# EMAT_K1.net
KiCad netlist of a schematic drawn in Altium Designer
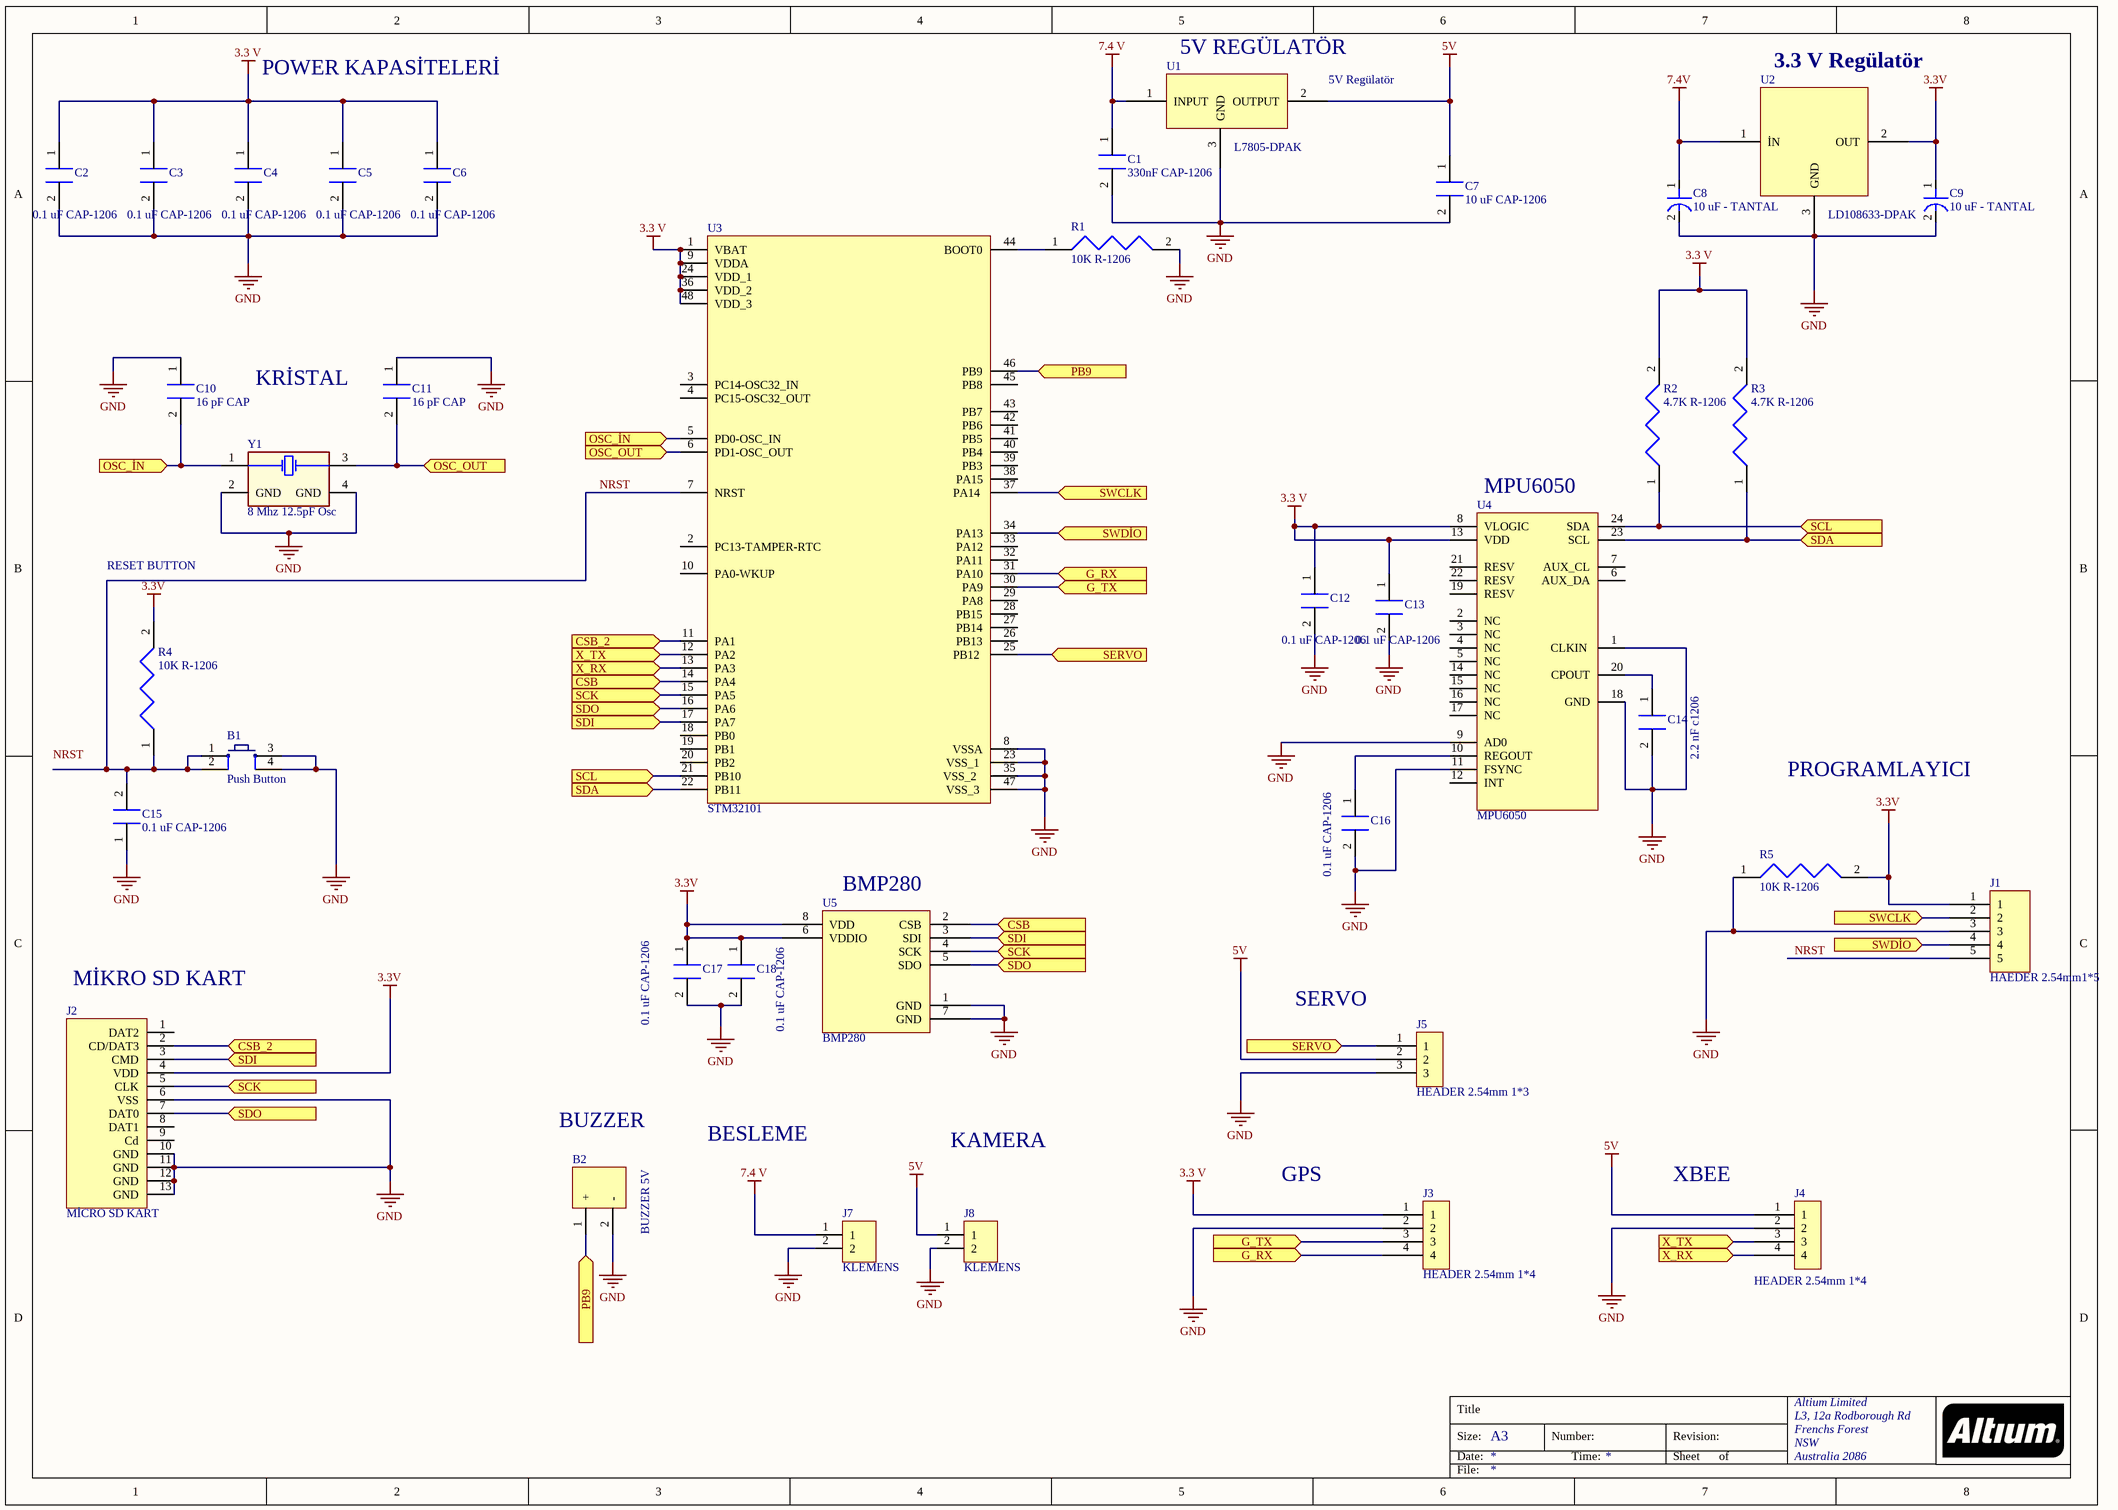
[diagram p0: ŞEMATİK1.SchDoc]

(export (version "E")
  (design (tool "Eeschema 10.0.6"))
  (components
    (comp (ref "B1")
      (value "Push Button")
      (footprint "PUSH BUTTON")
      (description "Smd Push Button")
      (libsource (lib "ŞEMATİK KÜTÜPHANE") (part "Push Button"))
    )
    (comp (ref "B2")
      (value "BUZZER 5V")
      (footprint "BUZZER")
      (description "1*2")
      (libsource (lib "ŞEMATİK KÜTÜPHANE") (part "BUZZER 5V"))
    )
    (comp (ref "C1")
      (value "330nF CAP-1206")
      (footprint "CAP-1206")
      (description "330nF 1206")
      (libsource (lib "ŞEMATİK KÜTÜPHANE") (part "330nF CAP-1206"))
    )
    (comp (ref "C2")
      (value "0.1 uF CAP-1206")
      (footprint "CAP-1206")
      (description "0.1 uF 1206")
      (libsource (lib "ŞEMATİK KÜTÜPHANE") (part "0.1 uF CAP-1206"))
    )
    (comp (ref "C3")
      (value "0.1 uF CAP-1206")
      (footprint "CAP-1206")
      (description "0.1 uF 1206")
      (libsource (lib "ŞEMATİK KÜTÜPHANE") (part "0.1 uF CAP-1206"))
    )
    (comp (ref "C4")
      (value "0.1 uF CAP-1206")
      (footprint "CAP-1206")
      (description "0.1 uF 1206")
      (libsource (lib "ŞEMATİK KÜTÜPHANE") (part "0.1 uF CAP-1206"))
    )
    (comp (ref "C5")
      (value "0.1 uF CAP-1206")
      (footprint "CAP-1206")
      (description "0.1 uF 1206")
      (libsource (lib "ŞEMATİK KÜTÜPHANE") (part "0.1 uF CAP-1206"))
    )
    (comp (ref "C6")
      (value "0.1 uF CAP-1206")
      (footprint "CAP-1206")
      (description "0.1 uF 1206")
      (libsource (lib "ŞEMATİK KÜTÜPHANE") (part "0.1 uF CAP-1206"))
    )
    (comp (ref "C7")
      (value "10 uF CAP-1206")
      (footprint "CAP-1206")
      (libsource (lib "ŞEMATİK KÜTÜPHANE") (part "10 uF CAP-1206"))
    )
    (comp (ref "C8")
      (value "10 uF - TANTAL")
      (footprint "CAP-1206 TANTAL")
      (description "KUTUPLU")
      (libsource (lib "ŞEMATİK KÜTÜPHANE") (part "10 uF - TANTAL"))
    )
    (comp (ref "C9")
      (value "10 uF - TANTAL")
      (footprint "CAP-1206 TANTAL")
      (description "KUTUPLU")
      (libsource (lib "ŞEMATİK KÜTÜPHANE") (part "10 uF - TANTAL"))
    )
    (comp (ref "C10")
      (value "16 pF CAP")
      (footprint "16pF CAP")
      (description "16pF Capasitör")
      (libsource (lib "ŞEMATİK KÜTÜPHANE") (part "16 pF CAP"))
    )
    (comp (ref "C11")
      (value "16 pF CAP")
      (footprint "16pF CAP")
      (description "16pF Capasitör")
      (libsource (lib "ŞEMATİK KÜTÜPHANE") (part "16 pF CAP"))
    )
    (comp (ref "C12")
      (value "0.1 uF CAP-1206")
      (footprint "CAP-1206")
      (description "0.1 uF 1206")
      (libsource (lib "ŞEMATİK KÜTÜPHANE") (part "0.1 uF CAP-1206"))
    )
    (comp (ref "C13")
      (value "0.1 uF CAP-1206")
      (footprint "CAP-1206")
      (description "0.1 uF 1206")
      (libsource (lib "ŞEMATİK KÜTÜPHANE") (part "0.1 uF CAP-1206"))
    )
    (comp (ref "C14")
      (value "2.2 nF c1206")
      (footprint "CAP-1206")
      (libsource (lib "ŞEMATİK KÜTÜPHANE") (part "2.2 nF c1206"))
    )
    (comp (ref "C15")
      (value "0.1 uF CAP-1206")
      (footprint "CAP-1206")
      (description "0.1 uF 1206")
      (libsource (lib "ŞEMATİK KÜTÜPHANE") (part "0.1 uF CAP-1206"))
    )
    (comp (ref "C16")
      (value "0.1 uF CAP-1206")
      (footprint "CAP-1206")
      (description "0.1 uF 1206")
      (libsource (lib "ŞEMATİK KÜTÜPHANE") (part "0.1 uF CAP-1206"))
    )
    (comp (ref "C17")
      (value "0.1 uF CAP-1206")
      (footprint "CAP-1206")
      (description "0.1 uF 1206")
      (libsource (lib "ŞEMATİK KÜTÜPHANE") (part "0.1 uF CAP-1206"))
    )
    (comp (ref "C18")
      (value "0.1 uF CAP-1206")
      (footprint "CAP-1206")
      (description "0.1 uF 1206")
      (libsource (lib "ŞEMATİK KÜTÜPHANE") (part "0.1 uF CAP-1206"))
    )
    (comp (ref "J1")
      (value "HAEDER 2.54mm1*5")
      (footprint "FEMALE HEADER 1*5 2.54 MM")
      (description "5 PİNLİ")
      (libsource (lib "ŞEMATİK KÜTÜPHANE") (part "HAEDER 2.54mm1*5"))
    )
    (comp (ref "J2")
      (value "MİCRO SD KART")
      (footprint "MİCRO SD KART")
      (description "SD HOLDER")
      (libsource (lib "ŞEMATİK KÜTÜPHANE") (part "MİCRO SD KART"))
    )
    (comp (ref "J3")
      (value "HEADER 2.54mm 1*4")
      (footprint "FEMALE HEADER 1*4 2.54MM")
      (description "4 PİNLİ")
      (libsource (lib "ŞEMATİK KÜTÜPHANE") (part "HEADER 2.54mm 1*4"))
    )
    (comp (ref "J4")
      (value "HEADER 2.54mm 1*4")
      (footprint "FEMALE HEADER 1*4 2.54MM")
      (description "4 PİNLİ")
      (libsource (lib "ŞEMATİK KÜTÜPHANE") (part "HEADER 2.54mm 1*4"))
    )
    (comp (ref "J5")
      (value "HEADER 2.54mm 1*3")
      (footprint "FEMALE HEADER 1*3 2.54MM")
      (description "3 PİNLİ")
      (libsource (lib "ŞEMATİK KÜTÜPHANE") (part "HEADER 2.54mm 1*3"))
    )
    (comp (ref "J7")
      (value "KLEMENS")
      (footprint "KLEMENS 1*2 / 3.5mm")
      (description "1*2/ 3.5MM")
      (libsource (lib "ŞEMATİK KÜTÜPHANE") (part "KLEMENS"))
    )
    (comp (ref "J8")
      (value "KLEMENS")
      (footprint "KLEMENS 1*2 / 3.5mm")
      (description "1*2/ 3.5MM")
      (libsource (lib "ŞEMATİK KÜTÜPHANE") (part "KLEMENS"))
    )
    (comp (ref "R1")
      (value "10K R-1206")
      (footprint "RES 1206")
      (libsource (lib "ŞEMATİK KÜTÜPHANE") (part "10K R-1206"))
    )
    (comp (ref "R2")
      (value "4.7K R-1206")
      (footprint "RES 1206")
      (libsource (lib "ŞEMATİK KÜTÜPHANE") (part "4.7K R-1206"))
    )
    (comp (ref "R3")
      (value "4.7K R-1206")
      (footprint "RES 1206")
      (libsource (lib "ŞEMATİK KÜTÜPHANE") (part "4.7K R-1206"))
    )
    (comp (ref "R4")
      (value "10K R-1206")
      (footprint "RES 1206")
      (libsource (lib "ŞEMATİK KÜTÜPHANE") (part "10K R-1206"))
    )
    (comp (ref "R5")
      (value "10K R-1206")
      (footprint "RES 1206")
      (libsource (lib "ŞEMATİK KÜTÜPHANE") (part "10K R-1206"))
    )
    (comp (ref "U1")
      (value "L7805-DPAK")
      (footprint "DPAKL7805 REGULATOR")
      (description "5V REGÜLATÖR DPAK")
      (libsource (lib "ŞEMATİK KÜTÜPHANE") (part "L7805-DPAK"))
    )
    (comp (ref "U2")
      (value "LD108633-DPAK")
      (footprint "DPAKL7805 REGULATOR")
      (description "3.3V  REGÜLATÖR")
      (libsource (lib "ŞEMATİK KÜTÜPHANE") (part "LD108633-DPAK"))
    )
    (comp (ref "U3")
      (value "STM32101")
      (footprint "FQP48")
      (description "STM32F48 101 İŞLEMCİ")
      (libsource (lib "ŞEMATİK KÜTÜPHANE") (part "STM32101"))
    )
    (comp (ref "U4")
      (value "MPU6050")
      (footprint "MPU6050-QFN")
      (description "QFNP 6*6 İŞLEMCİ")
      (libsource (lib "ŞEMATİK KÜTÜPHANE") (part "MPU6050"))
    )
    (comp (ref "U5")
      (value "BMP280")
      (footprint "BMP-280")
      (description "BMP280 SENSOR")
      (libsource (lib "ŞEMATİK KÜTÜPHANE") (part "BMP280"))
    )
    (comp (ref "Y1")
      (value "8 Mhz 12.5pF Osc")
      (footprint "8 Mhz 12.5pF OSC")
      (libsource (lib "ŞEMATİK KÜTÜPHANE") (part "8 Mhz 12.5pF Osc"))
    )
  )
  (nets
    (net (code "1") (name "/CSB") (class "Default")
      (node (ref "U3") (pin "14") (pinfunction "PA4_14") (pintype "passive"))
      (node (ref "U5") (pin "2") (pinfunction "CSB_2") (pintype "passive"))
    )
    (net (code "2") (name "/CSB_2") (class "Default")
      (node (ref "J2") (pin "2") (pinfunction "CD/DAT3_2") (pintype "passive"))
      (node (ref "U3") (pin "11") (pinfunction "PA1_11") (pintype "passive"))
    )
    (net (code "3") (name "/G_RX") (class "Default")
      (node (ref "J3") (pin "4") (pinfunction "4_4") (pintype "passive"))
      (node (ref "U3") (pin "31") (pinfunction "PA10_31") (pintype "passive"))
    )
    (net (code "4") (name "/G_TX") (class "Default")
      (node (ref "J3") (pin "3") (pinfunction "3_3") (pintype "passive"))
      (node (ref "U3") (pin "30") (pinfunction "PA9_30") (pintype "passive"))
    )
    (net (code "5") (name "/NRST") (class "Default")
      (node (ref "B1") (pin "1") (pinfunction "1_1") (pintype "passive"))
      (node (ref "B1") (pin "2") (pinfunction "2_2") (pintype "passive"))
      (node (ref "C15") (pin "2") (pinfunction "2_2") (pintype "passive"))
      (node (ref "J1") (pin "5") (pinfunction "5_5") (pintype "passive"))
      (node (ref "R4") (pin "1") (pinfunction "1_1") (pintype "passive"))
      (node (ref "U3") (pin "7") (pinfunction "NRST_7") (pintype "passive"))
    )
    (net (code "6") (name "/OSC_OUT") (class "Default")
      (node (ref "C11") (pin "2") (pinfunction "2_2") (pintype "passive"))
      (node (ref "U3") (pin "6") (pinfunction "PD1-OSC_OUT_6") (pintype "passive"))
      (node (ref "Y1") (pin "3") (pintype "passive"))
    )
    (net (code "7") (name "/OSC_İN") (class "Default")
      (node (ref "C10") (pin "2") (pinfunction "2_2") (pintype "passive"))
      (node (ref "U3") (pin "5") (pinfunction "PD0-OSC_IN_5") (pintype "passive"))
      (node (ref "Y1") (pin "1") (pintype "power_in"))
    )
    (net (code "8") (name "/PB9") (class "Default")
      (node (ref "B2") (pin "1") (pinfunction "+_1") (pintype "passive"))
      (node (ref "U3") (pin "46") (pinfunction "PB9_46") (pintype "passive"))
    )
    (net (code "9") (name "/SCK") (class "Default")
      (node (ref "J2") (pin "5") (pinfunction "CLK_5") (pintype "passive"))
      (node (ref "U3") (pin "15") (pinfunction "PA5_15") (pintype "passive"))
      (node (ref "U5") (pin "4") (pinfunction "SCK_4") (pintype "passive"))
    )
    (net (code "10") (name "/SCL") (class "Default")
      (node (ref "R2") (pin "1") (pinfunction "1_1") (pintype "passive"))
      (node (ref "U3") (pin "21") (pinfunction "PB10_21") (pintype "passive"))
      (node (ref "U4") (pin "24") (pinfunction "SDA_24") (pintype "passive"))
    )
    (net (code "11") (name "/SDA") (class "Default")
      (node (ref "R3") (pin "1") (pinfunction "1_1") (pintype "passive"))
      (node (ref "U3") (pin "22") (pinfunction "PB11_22") (pintype "passive"))
      (node (ref "U4") (pin "23") (pinfunction "SCL_23") (pintype "passive"))
    )
    (net (code "12") (name "/SDI") (class "Default")
      (node (ref "J2") (pin "3") (pinfunction "CMD_3") (pintype "passive"))
      (node (ref "U3") (pin "17") (pinfunction "PA7_17") (pintype "passive"))
      (node (ref "U5") (pin "3") (pinfunction "SDI_3") (pintype "passive"))
    )
    (net (code "13") (name "/SDO") (class "Default")
      (node (ref "J2") (pin "7") (pinfunction "DAT0_7") (pintype "passive"))
      (node (ref "U3") (pin "16") (pinfunction "PA6_16") (pintype "passive"))
      (node (ref "U5") (pin "5") (pinfunction "SDO_5") (pintype "passive"))
    )
    (net (code "14") (name "/SERVO") (class "Default")
      (node (ref "J5") (pin "1") (pinfunction "1_1") (pintype "passive"))
      (node (ref "U3") (pin "25") (pinfunction "PB12_25") (pintype "passive"))
    )
    (net (code "15") (name "/SWCLK") (class "Default")
      (node (ref "J1") (pin "2") (pinfunction "2_2") (pintype "passive"))
      (node (ref "U3") (pin "37") (pinfunction "PA14_37") (pintype "passive"))
    )
    (net (code "16") (name "/SWDİO") (class "Default")
      (node (ref "J1") (pin "4") (pinfunction "4_4") (pintype "passive"))
      (node (ref "U3") (pin "34") (pinfunction "PA13_34") (pintype "passive"))
    )
    (net (code "17") (name "/X_RX") (class "Default")
      (node (ref "J4") (pin "4") (pinfunction "4_4") (pintype "passive"))
      (node (ref "U3") (pin "13") (pinfunction "PA3_13") (pintype "passive"))
    )
    (net (code "18") (name "/X_TX") (class "Default")
      (node (ref "J4") (pin "3") (pinfunction "3_3") (pintype "passive"))
      (node (ref "U3") (pin "12") (pinfunction "PA2_12") (pintype "passive"))
    )
    (net (code "19") (name "3.3 V") (class "Default")
      (node (ref "C12") (pin "1") (pinfunction "1_1") (pintype "passive"))
      (node (ref "C13") (pin "1") (pinfunction "1_1") (pintype "passive"))
      (node (ref "C2") (pin "1") (pinfunction "1_1") (pintype "passive"))
      (node (ref "C3") (pin "1") (pinfunction "1_1") (pintype "passive"))
      (node (ref "C4") (pin "1") (pinfunction "1_1") (pintype "passive"))
      (node (ref "C5") (pin "1") (pinfunction "1_1") (pintype "passive"))
      (node (ref "C6") (pin "1") (pinfunction "1_1") (pintype "passive"))
      (node (ref "J3") (pin "1") (pinfunction "1_1") (pintype "passive"))
      (node (ref "R2") (pin "2") (pinfunction "2_2") (pintype "passive"))
      (node (ref "R3") (pin "2") (pinfunction "2_2") (pintype "passive"))
      (node (ref "U3") (pin "1") (pinfunction "VBAT_1") (pintype "passive"))
      (node (ref "U3") (pin "24") (pinfunction "VDD_1_24") (pintype "passive"))
      (node (ref "U3") (pin "36") (pinfunction "VDD_2_36") (pintype "passive"))
      (node (ref "U3") (pin "48") (pinfunction "VDD_3_48") (pintype "passive"))
      (node (ref "U3") (pin "9") (pinfunction "VDDA_9") (pintype "passive"))
      (node (ref "U4") (pin "13") (pinfunction "VDD_13") (pintype "passive"))
      (node (ref "U4") (pin "8") (pinfunction "VLOGIC_8") (pintype "passive"))
    )
    (net (code "20") (name "3.3V") (class "Default")
      (node (ref "C17") (pin "1") (pinfunction "1_1") (pintype "passive"))
      (node (ref "C18") (pin "1") (pinfunction "1_1") (pintype "passive"))
      (node (ref "C9") (pin "1") (pinfunction "1_1") (pintype "passive"))
      (node (ref "J1") (pin "1") (pinfunction "1_1") (pintype "passive"))
      (node (ref "J2") (pin "4") (pinfunction "VDD_4") (pintype "passive"))
      (node (ref "R4") (pin "2") (pinfunction "2_2") (pintype "passive"))
      (node (ref "R5") (pin "2") (pinfunction "2_2") (pintype "passive"))
      (node (ref "U2") (pin "2") (pinfunction "OUT_2") (pintype "passive"))
      (node (ref "U5") (pin "6") (pinfunction "VDDIO_6") (pintype "passive"))
      (node (ref "U5") (pin "8") (pinfunction "VDD_8") (pintype "passive"))
    )
    (net (code "21") (name "5V") (class "Default")
      (node (ref "C7") (pin "1") (pinfunction "1_1") (pintype "passive"))
      (node (ref "J4") (pin "1") (pinfunction "1_1") (pintype "passive"))
      (node (ref "J5") (pin "2") (pinfunction "2_2") (pintype "passive"))
      (node (ref "J8") (pin "1") (pinfunction "1_1") (pintype "passive"))
      (node (ref "U1") (pin "2") (pinfunction "OUTPUT_2") (pintype "passive"))
    )
    (net (code "22") (name "7.4 V") (class "Default")
      (node (ref "C1") (pin "1") (pinfunction "1_1") (pintype "passive"))
      (node (ref "J7") (pin "1") (pinfunction "1_1") (pintype "passive"))
      (node (ref "U1") (pin "1") (pinfunction "INPUT_1") (pintype "passive"))
    )
    (net (code "23") (name "7.4V") (class "Default")
      (node (ref "C8") (pin "1") (pinfunction "1_1") (pintype "passive"))
      (node (ref "U2") (pin "1") (pinfunction "İN_1") (pintype "passive"))
    )
    (net (code "24") (name "GND") (class "Default")
      (node (ref "B1") (pin "3") (pinfunction "3_3") (pintype "passive"))
      (node (ref "B1") (pin "4") (pinfunction "4_4") (pintype "passive"))
      (node (ref "B2") (pin "2") (pinfunction "-_2") (pintype "passive"))
      (node (ref "C1") (pin "2") (pinfunction "2_2") (pintype "passive"))
      (node (ref "C10") (pin "1") (pinfunction "1_1") (pintype "passive"))
      (node (ref "C11") (pin "1") (pinfunction "1_1") (pintype "passive"))
      (node (ref "C12") (pin "2") (pinfunction "2_2") (pintype "passive"))
      (node (ref "C13") (pin "2") (pinfunction "2_2") (pintype "passive"))
      (node (ref "C14") (pin "2") (pinfunction "2_2") (pintype "passive"))
      (node (ref "C15") (pin "1") (pinfunction "1_1") (pintype "passive"))
      (node (ref "C16") (pin "2") (pinfunction "2_2") (pintype "passive"))
      (node (ref "C17") (pin "2") (pinfunction "2_2") (pintype "passive"))
      (node (ref "C18") (pin "2") (pinfunction "2_2") (pintype "passive"))
      (node (ref "C2") (pin "2") (pinfunction "2_2") (pintype "passive"))
      (node (ref "C3") (pin "2") (pinfunction "2_2") (pintype "passive"))
      (node (ref "C4") (pin "2") (pinfunction "2_2") (pintype "passive"))
      (node (ref "C5") (pin "2") (pinfunction "2_2") (pintype "passive"))
      (node (ref "C6") (pin "2") (pinfunction "2_2") (pintype "passive"))
      (node (ref "C7") (pin "2") (pinfunction "2_2") (pintype "passive"))
      (node (ref "C8") (pin "2") (pinfunction "2_2") (pintype "passive"))
      (node (ref "C9") (pin "2") (pinfunction "2_2") (pintype "passive"))
      (node (ref "J1") (pin "3") (pinfunction "3_3") (pintype "passive"))
      (node (ref "J2") (pin "10") (pinfunction "GND_10") (pintype "passive"))
      (node (ref "J2") (pin "11") (pinfunction "GND_11") (pintype "passive"))
      (node (ref "J2") (pin "12") (pinfunction "GND_12") (pintype "passive"))
      (node (ref "J2") (pin "13") (pinfunction "GND_13") (pintype "passive"))
      (node (ref "J2") (pin "6") (pinfunction "VSS_6") (pintype "passive"))
      (node (ref "J3") (pin "2") (pinfunction "2_2") (pintype "passive"))
      (node (ref "J4") (pin "2") (pinfunction "2_2") (pintype "passive"))
      (node (ref "J5") (pin "3") (pinfunction "3_3") (pintype "passive"))
      (node (ref "J7") (pin "2") (pinfunction "2_2") (pintype "passive"))
      (node (ref "J8") (pin "2") (pinfunction "2_2") (pintype "passive"))
      (node (ref "R1") (pin "2") (pinfunction "2_2") (pintype "passive"))
      (node (ref "R5") (pin "1") (pinfunction "1_1") (pintype "passive"))
      (node (ref "U1") (pin "3") (pinfunction "GND_3") (pintype "passive"))
      (node (ref "U2") (pin "3") (pinfunction "GND_3") (pintype "passive"))
      (node (ref "U3") (pin "23") (pinfunction "VSS_1_23") (pintype "passive"))
      (node (ref "U3") (pin "35") (pinfunction "VSS_2_35") (pintype "passive"))
      (node (ref "U3") (pin "47") (pinfunction "VSS_3_47") (pintype "passive"))
      (node (ref "U3") (pin "8") (pinfunction "VSSA_8") (pintype "passive"))
      (node (ref "U4") (pin "1") (pinfunction "CLKIN_1") (pintype "passive"))
      (node (ref "U4") (pin "11") (pinfunction "FSYNC_11") (pintype "passive"))
      (node (ref "U4") (pin "18") (pinfunction "GND_18") (pintype "passive"))
      (node (ref "U4") (pin "9") (pinfunction "AD0_9") (pintype "passive"))
      (node (ref "U5") (pin "1") (pinfunction "GND_1") (pintype "passive"))
      (node (ref "U5") (pin "7") (pinfunction "GND_7") (pintype "passive"))
      (node (ref "Y1") (pin "2") (pinfunction "GND_2") (pintype "power_in"))
      (node (ref "Y1") (pin "4") (pinfunction "GND_4") (pintype "passive"))
    )
    (net (code "25") (name "Net-(U3-BOOT0)") (class "Default")
      (node (ref "R1") (pin "1") (pinfunction "1_1") (pintype "passive"))
      (node (ref "U3") (pin "44") (pinfunction "BOOT0_44") (pintype "passive"))
    )
    (net (code "26") (name "Net-(U4-CPOUT)") (class "Default")
      (node (ref "C14") (pin "1") (pinfunction "1_1") (pintype "passive"))
      (node (ref "U4") (pin "20") (pinfunction "CPOUT_20") (pintype "passive"))
    )
    (net (code "27") (name "Net-(U4-REGOUT)") (class "Default")
      (node (ref "C16") (pin "1") (pinfunction "1_1") (pintype "passive"))
      (node (ref "U4") (pin "10") (pinfunction "REGOUT_10") (pintype "passive"))
    )
    (net (code "28") (name "unconnected-(J2-Cd-Pad9)") (class "Default")
      (node (ref "J2") (pin "9") (pinfunction "Cd_9") (pintype "passive"))
    )
    (net (code "29") (name "unconnected-(J2-DAT1-Pad8)") (class "Default")
      (node (ref "J2") (pin "8") (pinfunction "DAT1_8") (pintype "passive"))
    )
    (net (code "30") (name "unconnected-(J2-DAT2-Pad1)") (class "Default")
      (node (ref "J2") (pin "1") (pinfunction "DAT2_1") (pintype "passive"))
    )
    (net (code "31") (name "unconnected-(U3-PA0-WKUP-Pad10)") (class "Default")
      (node (ref "U3") (pin "10") (pinfunction "PA0-WKUP_10") (pintype "passive"))
    )
    (net (code "32") (name "unconnected-(U3-PA8-Pad29)") (class "Default")
      (node (ref "U3") (pin "29") (pinfunction "PA8_29") (pintype "passive"))
    )
    (net (code "33") (name "unconnected-(U3-PA11-Pad32)") (class "Default")
      (node (ref "U3") (pin "32") (pinfunction "PA11_32") (pintype "passive"))
    )
    (net (code "34") (name "unconnected-(U3-PA12-Pad33)") (class "Default")
      (node (ref "U3") (pin "33") (pinfunction "PA12_33") (pintype "passive"))
    )
    (net (code "35") (name "unconnected-(U3-PA15-Pad38)") (class "Default")
      (node (ref "U3") (pin "38") (pinfunction "PA15_38") (pintype "passive"))
    )
    (net (code "36") (name "unconnected-(U3-PB0-Pad18)") (class "Default")
      (node (ref "U3") (pin "18") (pinfunction "PB0_18") (pintype "passive"))
    )
    (net (code "37") (name "unconnected-(U3-PB1-Pad19)") (class "Default")
      (node (ref "U3") (pin "19") (pinfunction "PB1_19") (pintype "passive"))
    )
    (net (code "38") (name "unconnected-(U3-PB2-Pad20)") (class "Default")
      (node (ref "U3") (pin "20") (pinfunction "PB2_20") (pintype "passive"))
    )
    (net (code "39") (name "unconnected-(U3-PB3-Pad39)") (class "Default")
      (node (ref "U3") (pin "39") (pinfunction "PB3_39") (pintype "passive"))
    )
    (net (code "40") (name "unconnected-(U3-PB4-Pad40)") (class "Default")
      (node (ref "U3") (pin "40") (pinfunction "PB4_40") (pintype "passive"))
    )
    (net (code "41") (name "unconnected-(U3-PB5-Pad41)") (class "Default")
      (node (ref "U3") (pin "41") (pinfunction "PB5_41") (pintype "passive"))
    )
    (net (code "42") (name "unconnected-(U3-PB6-Pad42)") (class "Default")
      (node (ref "U3") (pin "42") (pinfunction "PB6_42") (pintype "passive"))
    )
    (net (code "43") (name "unconnected-(U3-PB7-Pad43)") (class "Default")
      (node (ref "U3") (pin "43") (pinfunction "PB7_43") (pintype "passive"))
    )
    (net (code "44") (name "unconnected-(U3-PB8-Pad45)") (class "Default")
      (node (ref "U3") (pin "45") (pinfunction "PB8_45") (pintype "passive"))
    )
    (net (code "45") (name "unconnected-(U3-PB13-Pad26)") (class "Default")
      (node (ref "U3") (pin "26") (pinfunction "PB13_26") (pintype "passive"))
    )
    (net (code "46") (name "unconnected-(U3-PB14-Pad27)") (class "Default")
      (node (ref "U3") (pin "27") (pinfunction "PB14_27") (pintype "passive"))
    )
    (net (code "47") (name "unconnected-(U3-PB15-Pad28)") (class "Default")
      (node (ref "U3") (pin "28") (pinfunction "PB15_28") (pintype "passive"))
    )
    (net (code "48") (name "unconnected-(U3-PC13-TAMPER-RTC-Pad2)") (class "Default")
      (node (ref "U3") (pin "2") (pinfunction "PC13-TAMPER-RTC_2") (pintype "passive"))
    )
    (net (code "49") (name "unconnected-(U3-PC14-OSC32_IN-Pad3)") (class "Default")
      (node (ref "U3") (pin "3") (pinfunction "PC14-OSC32_IN_3") (pintype "passive"))
    )
    (net (code "50") (name "unconnected-(U3-PC15-OSC32_OUT-Pad4)") (class "Default")
      (node (ref "U3") (pin "4") (pinfunction "PC15-OSC32_OUT_4") (pintype "passive"))
    )
    (net (code "51") (name "unconnected-(U4-AUX_CL-Pad7)") (class "Default")
      (node (ref "U4") (pin "7") (pinfunction "AUX_CL_7") (pintype "passive"))
    )
    (net (code "52") (name "unconnected-(U4-AUX_DA-Pad6)") (class "Default")
      (node (ref "U4") (pin "6") (pinfunction "AUX_DA_6") (pintype "passive"))
    )
    (net (code "53") (name "unconnected-(U4-INT-Pad12)") (class "Default")
      (node (ref "U4") (pin "12") (pinfunction "INT_12") (pintype "passive"))
    )
    (net (code "54") (name "unconnected-(U4-NC-Pad2)") (class "Default")
      (node (ref "U4") (pin "2") (pinfunction "NC_2") (pintype "passive"))
    )
    (net (code "55") (name "unconnected-(U4-NC-Pad3)") (class "Default")
      (node (ref "U4") (pin "3") (pinfunction "NC_3") (pintype "passive"))
    )
    (net (code "56") (name "unconnected-(U4-NC-Pad4)") (class "Default")
      (node (ref "U4") (pin "4") (pinfunction "NC_4") (pintype "passive"))
    )
    (net (code "57") (name "unconnected-(U4-NC-Pad5)") (class "Default")
      (node (ref "U4") (pin "5") (pinfunction "NC_5") (pintype "passive"))
    )
    (net (code "58") (name "unconnected-(U4-NC-Pad14)") (class "Default")
      (node (ref "U4") (pin "14") (pinfunction "NC_14") (pintype "passive"))
    )
    (net (code "59") (name "unconnected-(U4-NC-Pad15)") (class "Default")
      (node (ref "U4") (pin "15") (pinfunction "NC_15") (pintype "passive"))
    )
    (net (code "60") (name "unconnected-(U4-NC-Pad16)") (class "Default")
      (node (ref "U4") (pin "16") (pinfunction "NC_16") (pintype "passive"))
    )
    (net (code "61") (name "unconnected-(U4-NC-Pad17)") (class "Default")
      (node (ref "U4") (pin "17") (pinfunction "NC_17") (pintype "passive"))
    )
    (net (code "62") (name "unconnected-(U4-RESV-Pad19)") (class "Default")
      (node (ref "U4") (pin "19") (pinfunction "RESV_19") (pintype "passive"))
    )
    (net (code "63") (name "unconnected-(U4-RESV-Pad21)") (class "Default")
      (node (ref "U4") (pin "21") (pinfunction "RESV_21") (pintype "passive"))
    )
    (net (code "64") (name "unconnected-(U4-RESV-Pad22)") (class "Default")
      (node (ref "U4") (pin "22") (pinfunction "RESV_22") (pintype "passive"))
    )
  )
)
